# ProPrj___2025-12-10.net
KiCad netlist of a schematic drawn in EasyEDA Pro
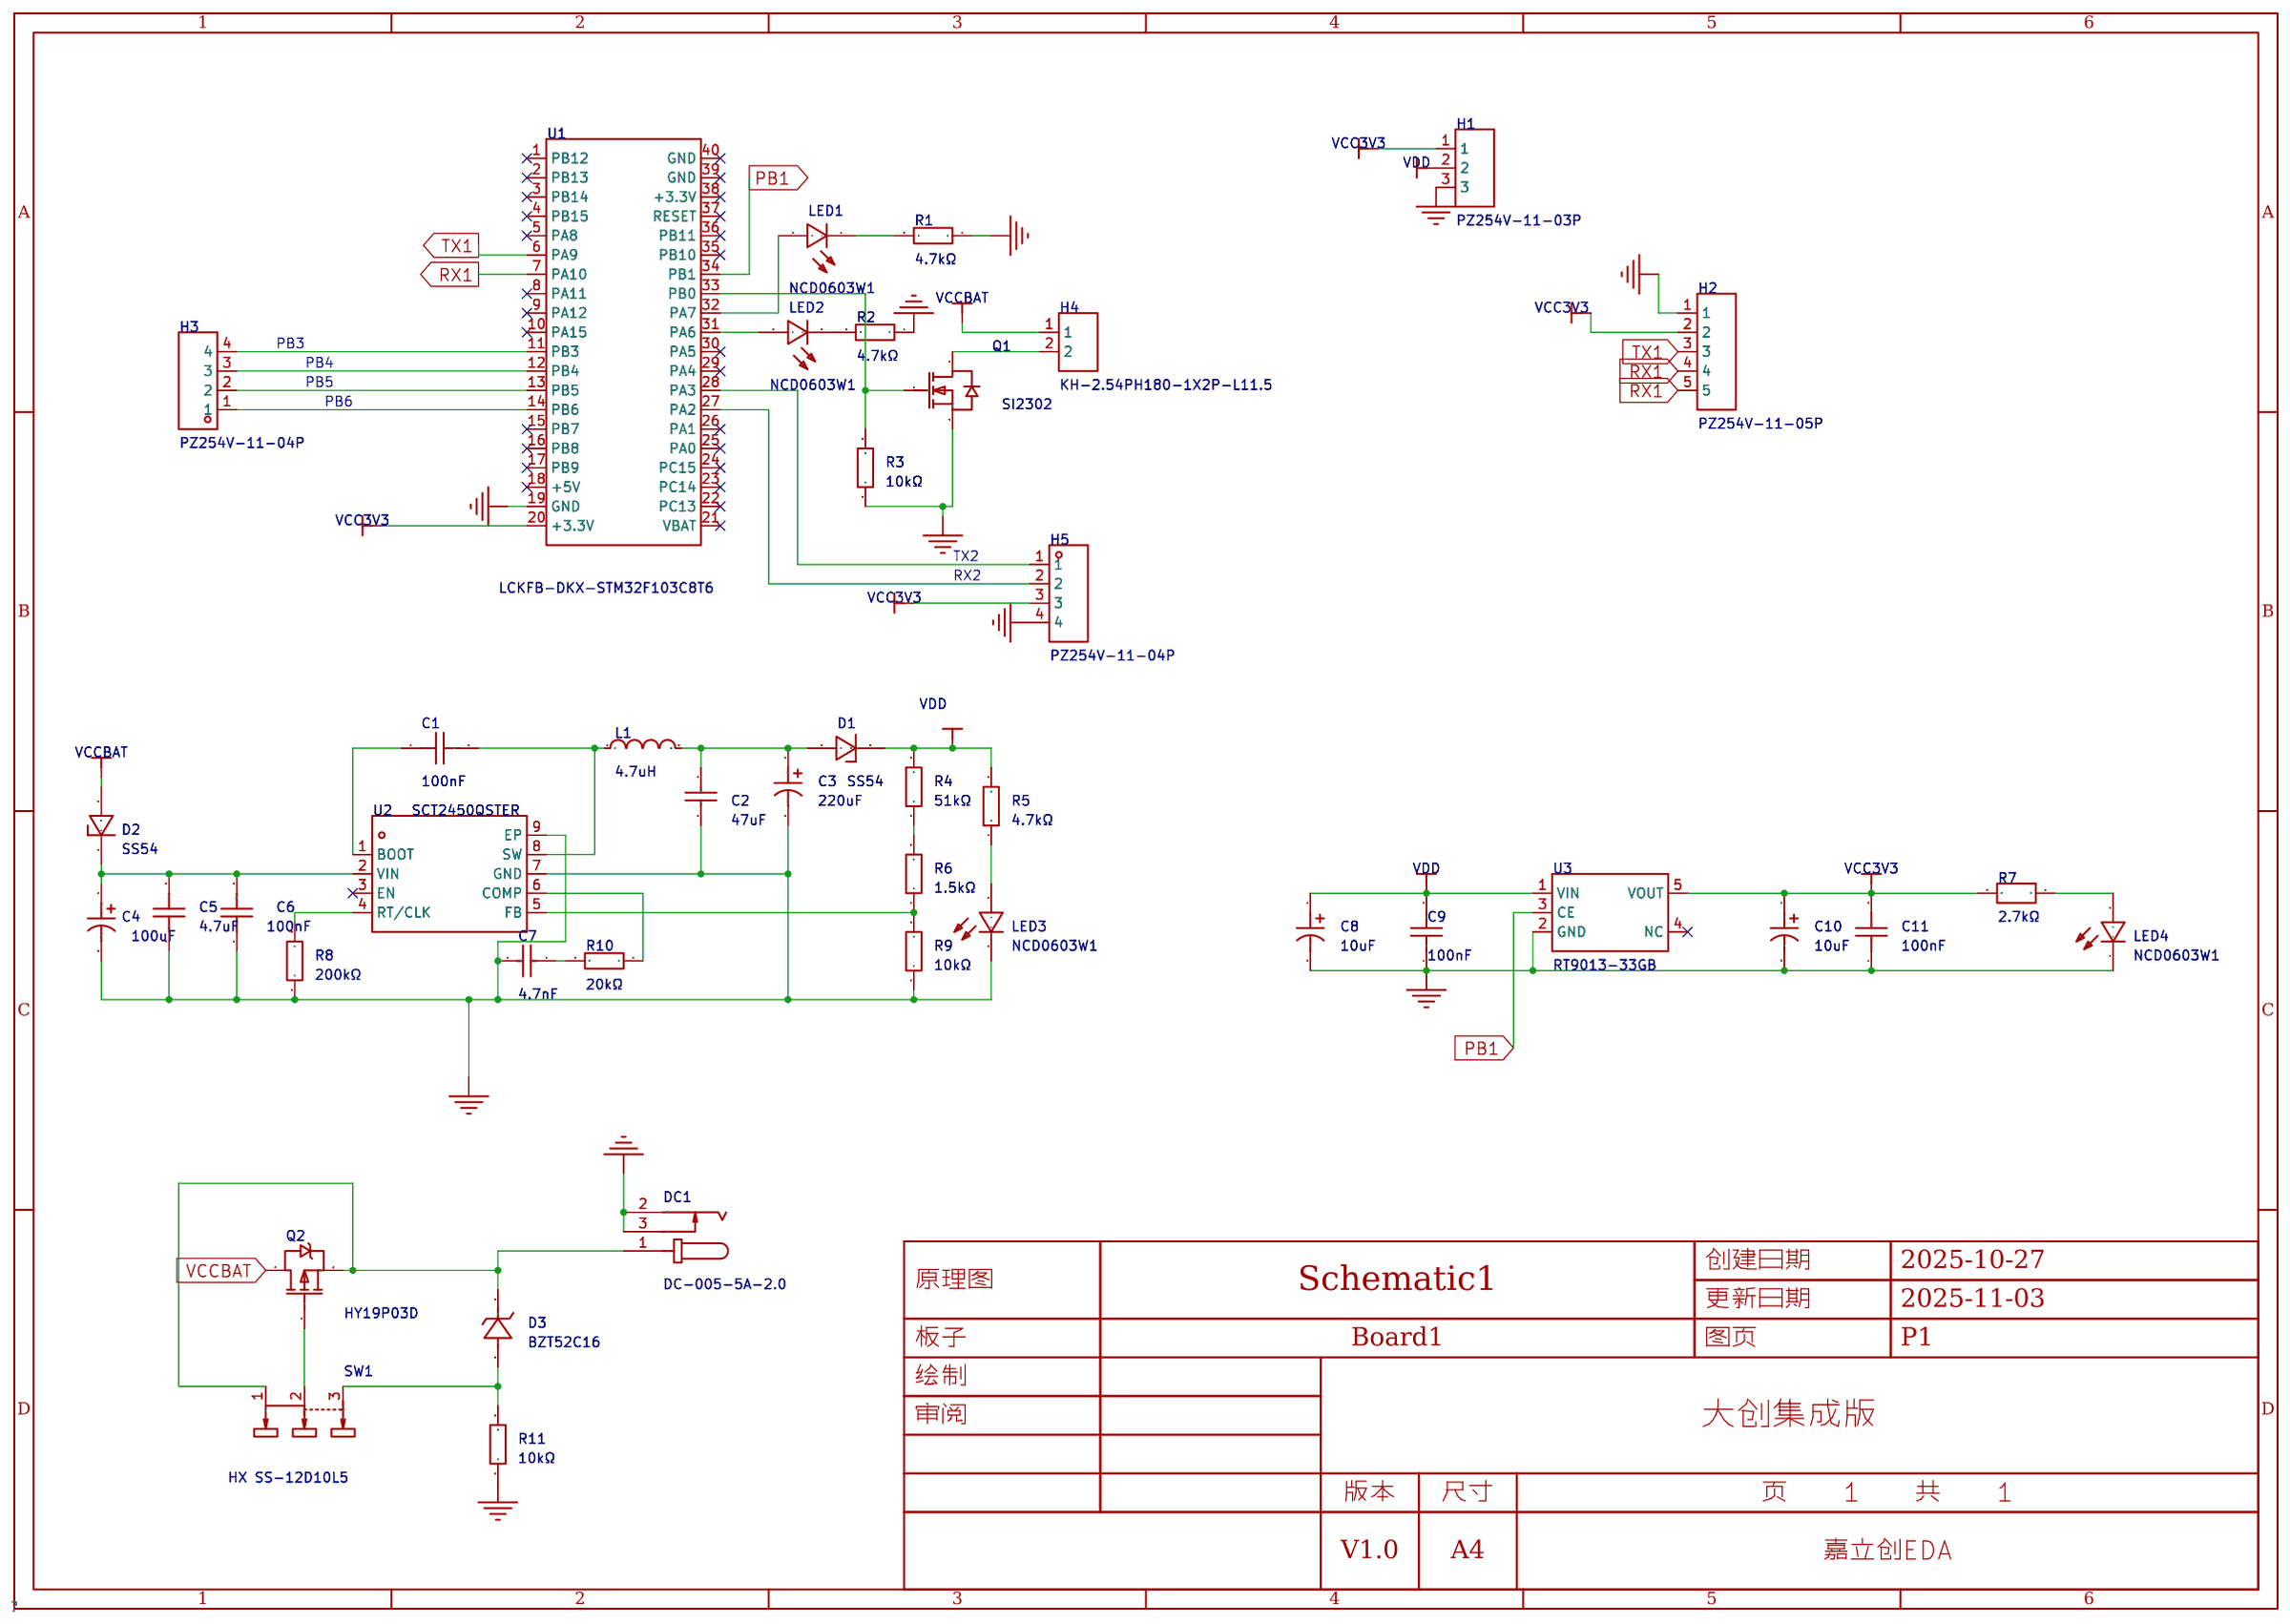
[diagram p0: schematic sheet]

(export (version "E")
  (design (tool "Eeschema 10.0.6"))
  (components
    (comp (ref "C1")
      (value "100nF")
      (footprint "easyedapro:C0603")
      (fields
        (field (name "Manufacturer Part") "CL10B104KB8NNNC")
        (field (name "Manufacturer") "SAMSUNG(三星)")
      )
      (libsource (lib "easyedapro") (part "CL10B104KB8NNNC"))
    )
    (comp (ref "C2")
      (value "47uF")
      (footprint "easyedapro:C0603")
      (fields
        (field (name "Manufacturer Part") "GRM188R60J476ME15D")
        (field (name "Manufacturer") "muRata(村田)")
      )
      (libsource (lib "easyedapro") (part "GRM188R60J476ME15D"))
    )
    (comp (ref "C3")
      (value "220uF")
      (footprint "easyedapro:CAP-SMD_BD6.3-L6.6-W6.6-LS7.3-FD-H7.7")
      (fields (field (name "Manufacturer Part") "JVJ25V220M6x8") (field (name "Manufacturer") "JIERR(捷而瑞)"))
      (libsource (lib "easyedapro") (part "JVJ25V220M6X8"))
    )
    (comp (ref "C4")
      (value "100uF")
      (footprint "easyedapro:CAP-SMD_BD6.3-L6.6-W6.6-FD-1")
      (fields (field (name "Manufacturer Part") "JVJ25V100M6x5") (field (name "Manufacturer") "JIERR(捷而瑞)"))
      (libsource (lib "easyedapro") (part "JVJ25V100M6X5"))
    )
    (comp (ref "C5")
      (value "4.7uF")
      (footprint "easyedapro:C0603")
      (fields
        (field (name "Manufacturer Part") "CL10A475KO8NNNC")
        (field (name "Manufacturer") "SAMSUNG(三星)")
      )
      (libsource (lib "easyedapro") (part "CL10A475KO8NNNC"))
    )
    (comp (ref "C6")
      (value "100nF")
      (footprint "easyedapro:C0603")
      (fields
        (field (name "Manufacturer Part") "CL10B104KB8NNNC")
        (field (name "Manufacturer") "SAMSUNG(三星)")
      )
      (libsource (lib "easyedapro") (part "CL10B104KB8NNNC"))
    )
    (comp (ref "C7")
      (value "4.7nF")
      (footprint "easyedapro:C0603")
      (fields (field (name "Manufacturer Part") "0603B472K500NT") (field (name "Manufacturer") "FH(风华)"))
      (libsource (lib "easyedapro") (part "0603B472K500NT"))
    )
    (comp (ref "C8")
      (value "10uF")
      (footprint "easyedapro:CAP-SMD_BD4.0-L4.3-W4.3-LS5.1-FD")
      (fields (field (name "Manufacturer Part") "JVJ25V10M4x6") (field (name "Manufacturer") "JIERR(捷而瑞)"))
      (libsource (lib "easyedapro") (part "JVJ25V10M4X6"))
    )
    (comp (ref "C9")
      (value "100nF")
      (footprint "easyedapro:C0603")
      (fields
        (field (name "Manufacturer Part") "CL10B104KB8NNNC")
        (field (name "Manufacturer") "SAMSUNG(三星)")
      )
      (libsource (lib "easyedapro") (part "CL10B104KB8NNNC"))
    )
    (comp (ref "C10")
      (value "10uF")
      (footprint "easyedapro:CAP-SMD_BD4.0-L4.3-W4.3-LS5.1-FD")
      (fields (field (name "Manufacturer Part") "JVJ25V10M4x6") (field (name "Manufacturer") "JIERR(捷而瑞)"))
      (libsource (lib "easyedapro") (part "JVJ25V10M4X6"))
    )
    (comp (ref "C11")
      (value "100nF")
      (footprint "easyedapro:C0603")
      (fields
        (field (name "Manufacturer Part") "CL10B104KB8NNNC")
        (field (name "Manufacturer") "SAMSUNG(三星)")
      )
      (libsource (lib "easyedapro") (part "CL10B104KB8NNNC"))
    )
    (comp (ref "D1")
      (value "SS54")
      (footprint "easyedapro:SMA_L4.3-W2.6-LS5.0-FD")
      (fields (field (name "Manufacturer") "R+O(宏嘉诚)"))
      (libsource (lib "easyedapro") (part "SS54_C7420369"))
    )
    (comp (ref "D2")
      (value "SS54")
      (footprint "easyedapro:SMA_L4.3-W2.6-LS5.0-FD")
      (fields (field (name "Manufacturer") "R+O(宏嘉诚)"))
      (libsource (lib "easyedapro") (part "SS54_C7420369"))
    )
    (comp (ref "D3")
      (value "BZT52C16")
      (footprint "easyedapro:SOD-123_L2.7-W1.6-LS3.7-RD")
      (fields (field (name "Manufacturer") "R+O(宏嘉诚)"))
      (libsource (lib "easyedapro") (part "BZT52C16_C19077413"))
    )
    (comp (ref "DC1")
      (value "DC-005-5A-2.0")
      (footprint "easyedapro:DC-IN-TH_DC-005-5A-2.0")
      (fields (field (name "Manufacturer") "XKB Connection(中国星坤)"))
      (libsource (lib "easyedapro") (part "DC-005-5A-2.0"))
    )
    (comp (ref "H1")
      (value "PZ254V-11-03P")
      (footprint "easyedapro:HDR-TH_3P-P2.54-V-M")
      (fields (field (name "Manufacturer") "XFCN(兴飞)"))
      (libsource (lib "easyedapro") (part "PZ254V-11-03P_C2937625"))
    )
    (comp (ref "H2")
      (value "PZ254V-11-05P")
      (footprint "easyedapro:HDR-TH_5P-P2.54-V-M")
      (fields (field (name "Manufacturer") "XFCN(兴飞)"))
      (libsource (lib "easyedapro") (part "PZ254V-11-05P"))
    )
    (comp (ref "H3")
      (value "PZ254V-11-04P")
      (footprint "easyedapro:HDR-TH_4P-P2.54-V-M")
      (fields (field (name "Manufacturer") "XFCN(兴飞)"))
      (libsource (lib "easyedapro") (part "PZ254V-11-04P_C2691448"))
    )
    (comp (ref "H4")
      (value "KH-2.54PH180-1X2P-L11.5")
      (footprint "easyedapro:HDR-TH_2P-P2.54-V-M")
      (fields (field (name "Manufacturer") "kinghelm(金航标)"))
      (libsource (lib "easyedapro") (part "KH-2.54PH180-1X2P-L11.5"))
    )
    (comp (ref "H5")
      (value "PZ254V-11-04P")
      (footprint "easyedapro:HDR-TH_4P-P2.54-V-M")
      (fields (field (name "Manufacturer") "XFCN(兴飞)"))
      (libsource (lib "easyedapro") (part "PZ254V-11-04P_C2691448"))
    )
    (comp (ref "L1")
      (value "4.7uH")
      (footprint "easyedapro:IND-SMD_L4.0-W4.0_FNR40XXS")
      (fields (field (name "Manufacturer Part") "FNR4030S4R7MT") (field (name "Manufacturer") "cjiang(长江微电)"))
      (libsource (lib "easyedapro") (part "FNR4030S4R7MT"))
    )
    (comp (ref "LED1")
      (value "NCD0603W1")
      (footprint "easyedapro:LED0603-RD")
      (fields (field (name "Manufacturer") "国星光电"))
      (libsource (lib "easyedapro") (part "NCD0603W1"))
    )
    (comp (ref "LED2")
      (value "NCD0603W1")
      (footprint "easyedapro:LED0603-RD")
      (fields (field (name "Manufacturer") "国星光电"))
      (libsource (lib "easyedapro") (part "NCD0603W1"))
    )
    (comp (ref "LED3")
      (value "NCD0603W1")
      (footprint "easyedapro:LED0603-RD")
      (fields (field (name "Manufacturer") "国星光电"))
      (libsource (lib "easyedapro") (part "NCD0603W1"))
    )
    (comp (ref "LED4")
      (value "NCD0603W1")
      (footprint "easyedapro:LED0603-RD")
      (fields (field (name "Manufacturer") "国星光电"))
      (libsource (lib "easyedapro") (part "NCD0603W1"))
    )
    (comp (ref "Q1")
      (value "SI2302")
      (footprint "easyedapro:SOT-23-3_L2.9-W1.3-P1.90-LS2.4-BR")
      (fields (field (name "Manufacturer") "YONGYUTAI(永裕泰)"))
      (libsource (lib "easyedapro") (part "SI2302_C2891732"))
    )
    (comp (ref "Q2")
      (value "HY19P03D")
      (footprint "easyedapro:TO-252-2_L6.6-W6.1-P4.57-LS9.9-TL-CW")
      (fields (field (name "Manufacturer") "HUAYI(华羿微)"))
      (libsource (lib "easyedapro") (part "HY19P03D"))
    )
    (comp (ref "R1")
      (value "4.7kΩ")
      (footprint "easyedapro:R0603")
      (fields
        (field (name "Manufacturer Part") "0603WAF4701T5E")
        (field (name "Manufacturer") "UNI-ROYAL(厚声)")
      )
      (libsource (lib "easyedapro") (part "0603WAF4701T5E"))
    )
    (comp (ref "R2")
      (value "4.7kΩ")
      (footprint "easyedapro:R0603")
      (fields
        (field (name "Manufacturer Part") "0603WAF4701T5E")
        (field (name "Manufacturer") "UNI-ROYAL(厚声)")
      )
      (libsource (lib "easyedapro") (part "0603WAF4701T5E"))
    )
    (comp (ref "R3")
      (value "10kΩ")
      (footprint "easyedapro:R0603")
      (fields
        (field (name "Manufacturer Part") "0603WAF1002T5E")
        (field (name "Manufacturer") "UNI-ROYAL(厚声)")
      )
      (libsource (lib "easyedapro") (part "0603WAF1002T5E"))
    )
    (comp (ref "R4")
      (value "51kΩ")
      (footprint "easyedapro:R0603")
      (fields
        (field (name "Manufacturer Part") "0603WAF5102T5E")
        (field (name "Manufacturer") "UNI-ROYAL(厚声)")
      )
      (libsource (lib "easyedapro") (part "0603WAF5102T5E"))
    )
    (comp (ref "R5")
      (value "4.7kΩ")
      (footprint "easyedapro:R0603")
      (fields
        (field (name "Manufacturer Part") "0603WAF4701T5E")
        (field (name "Manufacturer") "UNI-ROYAL(厚声)")
      )
      (libsource (lib "easyedapro") (part "0603WAF4701T5E"))
    )
    (comp (ref "R6")
      (value "1.5kΩ")
      (footprint "easyedapro:R0603")
      (fields
        (field (name "Manufacturer Part") "0603WAF1501T5E")
        (field (name "Manufacturer") "UNI-ROYAL(厚声)")
      )
      (libsource (lib "easyedapro") (part "0603WAF1501T5E"))
    )
    (comp (ref "R7")
      (value "2.7kΩ")
      (footprint "easyedapro:R0603")
      (fields (field (name "Manufacturer Part") "FRC0603F2701TS") (field (name "Manufacturer") "FOJAN(富捷)"))
      (libsource (lib "easyedapro") (part "FRC0603F2701TS"))
    )
    (comp (ref "R8")
      (value "200kΩ")
      (footprint "easyedapro:R0603")
      (fields
        (field (name "Manufacturer Part") "0603WAF2003T5E")
        (field (name "Manufacturer") "UNI-ROYAL(厚声)")
      )
      (libsource (lib "easyedapro") (part "0603WAF2003T5E"))
    )
    (comp (ref "R9")
      (value "10kΩ")
      (footprint "easyedapro:R0603")
      (fields
        (field (name "Manufacturer Part") "0603WAF1002T5E")
        (field (name "Manufacturer") "UNI-ROYAL(厚声)")
      )
      (libsource (lib "easyedapro") (part "0603WAF1002T5E"))
    )
    (comp (ref "R10")
      (value "20kΩ")
      (footprint "easyedapro:R0603")
      (fields
        (field (name "Manufacturer Part") "0603WAF2002T5E")
        (field (name "Manufacturer") "UNI-ROYAL(厚声)")
      )
      (libsource (lib "easyedapro") (part "0603WAF2002T5E"))
    )
    (comp (ref "R11")
      (value "10kΩ")
      (footprint "easyedapro:R0603")
      (fields
        (field (name "Manufacturer Part") "0603WAF1002T5E")
        (field (name "Manufacturer") "UNI-ROYAL(厚声)")
      )
      (libsource (lib "easyedapro") (part "0603WAF1002T5E"))
    )
    (comp (ref "SW1")
      (value "HX SS-12D10L5")
      (footprint "easyedapro:SW-TH_HX-SS-12D10L5")
      (fields (field (name "Manufacturer") "hanxia(韩下)"))
      (libsource (lib "easyedapro") (part "HX SS-12D10L5"))
    )
    (comp (ref "U1")
      (value "LCKFB-DKX-STM32F103C8T6")
      (footprint "easyedapro:CONN-TH_L53.3-W22.9_STM32F103C8T6-CARD")
      (fields (field (name "Manufacturer") "立创开发板"))
      (libsource (lib "easyedapro") (part "LCKFB-DKX-STM32F103C8T6"))
    )
    (comp (ref "U2")
      (value "SCT2450QSTER")
      (footprint "easyedapro:ESOP-8_L4.9-W3.9-P1.27-LS6.0-BL-EP")
      (fields (field (name "Manufacturer") "SCT(芯洲科技)"))
      (libsource (lib "easyedapro") (part "SCT2450QSTER"))
    )
    (comp (ref "U3")
      (value "RT9013-33GB")
      (footprint "easyedapro:SOT-23-5_L2.9-W1.6-P0.95-LS2.8-BR")
      (fields (field (name "Manufacturer") "TECH PUBLIC(台舟)"))
      (libsource (lib "easyedapro") (part "RT9013-33GB_C19268157"))
    )
  )
  (nets
    (net (code "1") (name "/PB3") (class "Default")
      (node (ref "H3") (pin "4") (pinfunction "4_4") (pintype "unspecified"))
      (node (ref "U1") (pin "11") (pinfunction "PB3_11") (pintype "unspecified"))
    )
    (net (code "2") (name "/PB4") (class "Default")
      (node (ref "H3") (pin "3") (pinfunction "3_3") (pintype "unspecified"))
      (node (ref "U1") (pin "12") (pinfunction "PB4_12") (pintype "unspecified"))
    )
    (net (code "3") (name "/PB5") (class "Default")
      (node (ref "H3") (pin "2") (pinfunction "2_2") (pintype "unspecified"))
      (node (ref "U1") (pin "13") (pinfunction "PB5_13") (pintype "unspecified"))
    )
    (net (code "4") (name "/PB6") (class "Default")
      (node (ref "H3") (pin "1") (pinfunction "1_1") (pintype "unspecified"))
      (node (ref "U1") (pin "14") (pinfunction "PB6_14") (pintype "unspecified"))
    )
    (net (code "5") (name "/RX2") (class "Default")
      (node (ref "H5") (pin "2") (pinfunction "2_2") (pintype "unspecified"))
      (node (ref "U1") (pin "27") (pinfunction "PA2_27") (pintype "unspecified"))
    )
    (net (code "6") (name "/TX2") (class "Default")
      (node (ref "H5") (pin "1") (pinfunction "1_1") (pintype "unspecified"))
      (node (ref "U1") (pin "28") (pinfunction "PA3_28") (pintype "unspecified"))
    )
    (net (code "7") (name "GND") (class "Default")
      (node (ref "C10") (pin "2") (pinfunction "2_2") (pintype "input"))
      (node (ref "C11") (pin "1") (pinfunction "1_1") (pintype "unspecified"))
      (node (ref "C2") (pin "1") (pinfunction "1_1") (pintype "input"))
      (node (ref "C3") (pin "2") (pinfunction "2_2") (pintype "input"))
      (node (ref "C4") (pin "2") (pinfunction "2_2") (pintype "input"))
      (node (ref "C5") (pin "1") (pinfunction "1_1") (pintype "unspecified"))
      (node (ref "C6") (pin "1") (pinfunction "1_1") (pintype "unspecified"))
      (node (ref "C7") (pin "1") (pinfunction "1_1") (pintype "input"))
      (node (ref "C8") (pin "2") (pinfunction "2_2") (pintype "input"))
      (node (ref "C9") (pin "1") (pinfunction "1_1") (pintype "unspecified"))
      (node (ref "DC1") (pin "2") (pinfunction "2_2") (pintype "unspecified"))
      (node (ref "DC1") (pin "3") (pinfunction "3_3") (pintype "unspecified"))
      (node (ref "H1") (pin "3") (pinfunction "3_3") (pintype "unspecified"))
      (node (ref "H2") (pin "1") (pinfunction "1_1") (pintype "unspecified"))
      (node (ref "H5") (pin "4") (pinfunction "4_4") (pintype "unspecified"))
      (node (ref "LED3") (pin "1") (pinfunction "-_1") (pintype "input"))
      (node (ref "LED4") (pin "1") (pinfunction "-_1") (pintype "input"))
      (node (ref "Q1") (pin "2") (pinfunction "S_2") (pintype "unspecified"))
      (node (ref "R1") (pin "1") (pinfunction "1_1") (pintype "input"))
      (node (ref "R11") (pin "1") (pinfunction "1_1") (pintype "input"))
      (node (ref "R2") (pin "1") (pinfunction "1_1") (pintype "input"))
      (node (ref "R3") (pin "1") (pinfunction "1_1") (pintype "input"))
      (node (ref "R8") (pin "1") (pinfunction "1_1") (pintype "input"))
      (node (ref "R9") (pin "1") (pinfunction "1_1") (pintype "input"))
      (node (ref "U1") (pin "19") (pinfunction "GND_19") (pintype "unspecified"))
      (node (ref "U2") (pin "7") (pinfunction "GND_7") (pintype "unspecified"))
      (node (ref "U2") (pin "9") (pinfunction "EP_9") (pintype "unspecified"))
      (node (ref "U3") (pin "2") (pinfunction "GND_2") (pintype "unspecified"))
    )
    (net (code "8") (name "Net-(C7-Pad2)") (class "Default")
      (node (ref "C7") (pin "2") (pinfunction "2_2") (pintype "input"))
      (node (ref "R10") (pin "2") (pinfunction "2_2") (pintype "input"))
    )
    (net (code "9") (name "Net-(D1-A)") (class "Default")
      (node (ref "C2") (pin "2") (pinfunction "2_2") (pintype "input"))
      (node (ref "C3") (pin "1") (pinfunction "1_1") (pintype "input"))
      (node (ref "D1") (pin "1") (pinfunction "A_1") (pintype "unspecified"))
      (node (ref "L1") (pin "2") (pinfunction "2_2") (pintype "unspecified"))
    )
    (net (code "10") (name "Net-(D2-K)") (class "Default")
      (node (ref "C4") (pin "1") (pinfunction "1_1") (pintype "input"))
      (node (ref "C5") (pin "2") (pinfunction "2_2") (pintype "unspecified"))
      (node (ref "C6") (pin "2") (pinfunction "2_2") (pintype "unspecified"))
      (node (ref "D2") (pin "2") (pinfunction "K_2") (pintype "unspecified"))
      (node (ref "U2") (pin "2") (pinfunction "VIN_2") (pintype "unspecified"))
    )
    (net (code "11") (name "Net-(D3-A)") (class "Default")
      (node (ref "D3") (pin "2") (pinfunction "A_2") (pintype "unspecified"))
      (node (ref "R11") (pin "2") (pinfunction "2_2") (pintype "input"))
      (node (ref "SW1") (pin "3") (pinfunction "3_3") (pintype "unspecified"))
    )
    (net (code "12") (name "Net-(D3-K)") (class "Default")
      (node (ref "D3") (pin "1") (pinfunction "K_1") (pintype "unspecified"))
      (node (ref "DC1") (pin "1") (pinfunction "1_1") (pintype "unspecified"))
      (node (ref "Q2") (pin "3") (pinfunction "S_3") (pintype "unspecified"))
      (node (ref "SW1") (pin "1") (pinfunction "1_1") (pintype "unspecified"))
    )
    (net (code "13") (name "Net-(LED1-+)") (class "Default")
      (node (ref "LED1") (pin "2") (pinfunction "+_2") (pintype "input"))
      (node (ref "U1") (pin "32") (pinfunction "PA7_32") (pintype "unspecified"))
    )
    (net (code "14") (name "Net-(LED1--)") (class "Default")
      (node (ref "LED1") (pin "1") (pinfunction "-_1") (pintype "input"))
      (node (ref "R1") (pin "2") (pinfunction "2_2") (pintype "input"))
    )
    (net (code "15") (name "Net-(LED2-+)") (class "Default")
      (node (ref "LED2") (pin "2") (pinfunction "+_2") (pintype "input"))
      (node (ref "U1") (pin "31") (pinfunction "PA6_31") (pintype "unspecified"))
    )
    (net (code "16") (name "Net-(LED2--)") (class "Default")
      (node (ref "LED2") (pin "1") (pinfunction "-_1") (pintype "input"))
      (node (ref "R2") (pin "2") (pinfunction "2_2") (pintype "input"))
    )
    (net (code "17") (name "Net-(LED3-+)") (class "Default")
      (node (ref "LED3") (pin "2") (pinfunction "+_2") (pintype "input"))
      (node (ref "R5") (pin "1") (pinfunction "1_1") (pintype "input"))
    )
    (net (code "18") (name "Net-(LED4-+)") (class "Default")
      (node (ref "LED4") (pin "2") (pinfunction "+_2") (pintype "input"))
      (node (ref "R7") (pin "1") (pinfunction "1_1") (pintype "unspecified"))
    )
    (net (code "19") (name "Net-(Q1-D)") (class "Default")
      (node (ref "H4") (pin "2") (pinfunction "2_2") (pintype "unspecified"))
      (node (ref "Q1") (pin "3") (pinfunction "D_3") (pintype "unspecified"))
    )
    (net (code "20") (name "Net-(Q1-G)") (class "Default")
      (node (ref "Q1") (pin "1") (pinfunction "G_1") (pintype "unspecified"))
      (node (ref "R3") (pin "2") (pinfunction "2_2") (pintype "input"))
      (node (ref "U1") (pin "33") (pinfunction "PB0_33") (pintype "unspecified"))
    )
    (net (code "21") (name "Net-(Q2-G)") (class "Default")
      (node (ref "Q2") (pin "1") (pinfunction "G_1") (pintype "unspecified"))
      (node (ref "SW1") (pin "2") (pinfunction "2_2") (pintype "unspecified"))
    )
    (net (code "22") (name "Net-(R4-Pad1)") (class "Default")
      (node (ref "R4") (pin "1") (pinfunction "1_1") (pintype "input"))
      (node (ref "R6") (pin "2") (pinfunction "2_2") (pintype "input"))
    )
    (net (code "23") (name "Net-(U2-BOOT)") (class "Default")
      (node (ref "C1") (pin "1") (pinfunction "1_1") (pintype "unspecified"))
      (node (ref "U2") (pin "1") (pinfunction "BOOT_1") (pintype "unspecified"))
    )
    (net (code "24") (name "Net-(U2-COMP)") (class "Default")
      (node (ref "R10") (pin "1") (pinfunction "1_1") (pintype "input"))
      (node (ref "U2") (pin "6") (pinfunction "COMP_6") (pintype "unspecified"))
    )
    (net (code "25") (name "Net-(U2-FB)") (class "Default")
      (node (ref "R6") (pin "1") (pinfunction "1_1") (pintype "input"))
      (node (ref "R9") (pin "2") (pinfunction "2_2") (pintype "input"))
      (node (ref "U2") (pin "5") (pinfunction "FB_5") (pintype "unspecified"))
    )
    (net (code "26") (name "Net-(U2-RT{slash}CLK)") (class "Default")
      (node (ref "R8") (pin "2") (pinfunction "2_2") (pintype "input"))
      (node (ref "U2") (pin "4") (pinfunction "RT/CLK_4") (pintype "unspecified"))
    )
    (net (code "27") (name "Net-(U2-SW)") (class "Default")
      (node (ref "C1") (pin "2") (pinfunction "2_2") (pintype "unspecified"))
      (node (ref "L1") (pin "1") (pinfunction "1_1") (pintype "unspecified"))
      (node (ref "U2") (pin "8") (pinfunction "SW_8") (pintype "unspecified"))
    )
    (net (code "28") (name "PB1") (class "Default")
      (node (ref "U1") (pin "34") (pinfunction "PB1_34") (pintype "unspecified"))
      (node (ref "U3") (pin "3") (pinfunction "CE_3") (pintype "unspecified"))
    )
    (net (code "29") (name "RX1") (class "Default")
      (node (ref "H2") (pin "4") (pinfunction "4_4") (pintype "unspecified"))
      (node (ref "H2") (pin "5") (pinfunction "5_5") (pintype "unspecified"))
      (node (ref "U1") (pin "7") (pinfunction "PA10_7") (pintype "unspecified"))
    )
    (net (code "30") (name "TX1") (class "Default")
      (node (ref "H2") (pin "3") (pinfunction "3_3") (pintype "unspecified"))
      (node (ref "U1") (pin "6") (pinfunction "PA9_6") (pintype "unspecified"))
    )
    (net (code "31") (name "VCC3V3") (class "Default")
      (node (ref "C10") (pin "1") (pinfunction "1_1") (pintype "input"))
      (node (ref "C11") (pin "2") (pinfunction "2_2") (pintype "unspecified"))
      (node (ref "H1") (pin "1") (pinfunction "1_1") (pintype "unspecified"))
      (node (ref "H2") (pin "2") (pinfunction "2_2") (pintype "unspecified"))
      (node (ref "H5") (pin "3") (pinfunction "3_3") (pintype "unspecified"))
      (node (ref "R7") (pin "2") (pinfunction "2_2") (pintype "unspecified"))
      (node (ref "U1") (pin "20") (pinfunction "+3.3V_20") (pintype "unspecified"))
      (node (ref "U3") (pin "5") (pinfunction "VOUT_5") (pintype "unspecified"))
    )
    (net (code "32") (name "VCCBAT") (class "Default")
      (node (ref "D2") (pin "1") (pinfunction "A_1") (pintype "unspecified"))
      (node (ref "H4") (pin "1") (pinfunction "1_1") (pintype "unspecified"))
      (node (ref "Q2") (pin "2") (pinfunction "D_2") (pintype "unspecified"))
    )
    (net (code "33") (name "VDD") (class "Default")
      (node (ref "C8") (pin "1") (pinfunction "1_1") (pintype "input"))
      (node (ref "C9") (pin "2") (pinfunction "2_2") (pintype "unspecified"))
      (node (ref "D1") (pin "2") (pinfunction "K_2") (pintype "unspecified"))
      (node (ref "H1") (pin "2") (pinfunction "2_2") (pintype "unspecified"))
      (node (ref "R4") (pin "2") (pinfunction "2_2") (pintype "input"))
      (node (ref "R5") (pin "2") (pinfunction "2_2") (pintype "input"))
      (node (ref "U3") (pin "1") (pinfunction "VIN_1") (pintype "unspecified"))
    )
    (net (code "34") (name "unconnected-(U1-+3.3V-Pad38)") (class "Default")
      (node (ref "U1") (pin "38") (pinfunction "+3.3V_38") (pintype "unspecified+no_connect"))
    )
    (net (code "35") (name "unconnected-(U1-+5V-Pad18)") (class "Default")
      (node (ref "U1") (pin "18") (pinfunction "+5V_18") (pintype "unspecified+no_connect"))
    )
    (net (code "36") (name "unconnected-(U1-GND-Pad39)") (class "Default")
      (node (ref "U1") (pin "39") (pinfunction "GND_39") (pintype "unspecified+no_connect"))
    )
    (net (code "37") (name "unconnected-(U1-GND-Pad40)") (class "Default")
      (node (ref "U1") (pin "40") (pinfunction "GND_40") (pintype "unspecified+no_connect"))
    )
    (net (code "38") (name "unconnected-(U1-PA0-Pad25)") (class "Default")
      (node (ref "U1") (pin "25") (pinfunction "PA0_25") (pintype "unspecified+no_connect"))
    )
    (net (code "39") (name "unconnected-(U1-PA1-Pad26)") (class "Default")
      (node (ref "U1") (pin "26") (pinfunction "PA1_26") (pintype "unspecified+no_connect"))
    )
    (net (code "40") (name "unconnected-(U1-PA4-Pad29)") (class "Default")
      (node (ref "U1") (pin "29") (pinfunction "PA4_29") (pintype "unspecified+no_connect"))
    )
    (net (code "41") (name "unconnected-(U1-PA5-Pad30)") (class "Default")
      (node (ref "U1") (pin "30") (pinfunction "PA5_30") (pintype "unspecified+no_connect"))
    )
    (net (code "42") (name "unconnected-(U1-PA8-Pad5)") (class "Default")
      (node (ref "U1") (pin "5") (pinfunction "PA8_5") (pintype "unspecified+no_connect"))
    )
    (net (code "43") (name "unconnected-(U1-PA11-Pad8)") (class "Default")
      (node (ref "U1") (pin "8") (pinfunction "PA11_8") (pintype "unspecified+no_connect"))
    )
    (net (code "44") (name "unconnected-(U1-PA12-Pad9)") (class "Default")
      (node (ref "U1") (pin "9") (pinfunction "PA12_9") (pintype "unspecified+no_connect"))
    )
    (net (code "45") (name "unconnected-(U1-PA15-Pad10)") (class "Default")
      (node (ref "U1") (pin "10") (pinfunction "PA15_10") (pintype "unspecified+no_connect"))
    )
    (net (code "46") (name "unconnected-(U1-PB7-Pad15)") (class "Default")
      (node (ref "U1") (pin "15") (pinfunction "PB7_15") (pintype "unspecified+no_connect"))
    )
    (net (code "47") (name "unconnected-(U1-PB8-Pad16)") (class "Default")
      (node (ref "U1") (pin "16") (pinfunction "PB8_16") (pintype "unspecified+no_connect"))
    )
    (net (code "48") (name "unconnected-(U1-PB9-Pad17)") (class "Default")
      (node (ref "U1") (pin "17") (pinfunction "PB9_17") (pintype "unspecified+no_connect"))
    )
    (net (code "49") (name "unconnected-(U1-PB10-Pad35)") (class "Default")
      (node (ref "U1") (pin "35") (pinfunction "PB10_35") (pintype "unspecified+no_connect"))
    )
    (net (code "50") (name "unconnected-(U1-PB11-Pad36)") (class "Default")
      (node (ref "U1") (pin "36") (pinfunction "PB11_36") (pintype "unspecified+no_connect"))
    )
    (net (code "51") (name "unconnected-(U1-PB12-Pad1)") (class "Default")
      (node (ref "U1") (pin "1") (pinfunction "PB12_1") (pintype "unspecified+no_connect"))
    )
    (net (code "52") (name "unconnected-(U1-PB13-Pad2)") (class "Default")
      (node (ref "U1") (pin "2") (pinfunction "PB13_2") (pintype "unspecified+no_connect"))
    )
    (net (code "53") (name "unconnected-(U1-PB14-Pad3)") (class "Default")
      (node (ref "U1") (pin "3") (pinfunction "PB14_3") (pintype "unspecified+no_connect"))
    )
    (net (code "54") (name "unconnected-(U1-PB15-Pad4)") (class "Default")
      (node (ref "U1") (pin "4") (pinfunction "PB15_4") (pintype "unspecified+no_connect"))
    )
    (net (code "55") (name "unconnected-(U1-PC13-Pad22)") (class "Default")
      (node (ref "U1") (pin "22") (pinfunction "PC13_22") (pintype "unspecified+no_connect"))
    )
    (net (code "56") (name "unconnected-(U1-PC14-Pad23)") (class "Default")
      (node (ref "U1") (pin "23") (pinfunction "PC14_23") (pintype "unspecified+no_connect"))
    )
    (net (code "57") (name "unconnected-(U1-PC15-Pad24)") (class "Default")
      (node (ref "U1") (pin "24") (pinfunction "PC15_24") (pintype "unspecified+no_connect"))
    )
    (net (code "58") (name "unconnected-(U1-RESET-Pad37)") (class "Default")
      (node (ref "U1") (pin "37") (pinfunction "RESET_37") (pintype "unspecified+no_connect"))
    )
    (net (code "59") (name "unconnected-(U1-VBAT-Pad21)") (class "Default")
      (node (ref "U1") (pin "21") (pinfunction "VBAT_21") (pintype "unspecified+no_connect"))
    )
    (net (code "60") (name "unconnected-(U2-EN-Pad3)") (class "Default")
      (node (ref "U2") (pin "3") (pinfunction "EN_3") (pintype "unspecified+no_connect"))
    )
    (net (code "61") (name "unconnected-(U3-NC-Pad4)") (class "Default")
      (node (ref "U3") (pin "4") (pinfunction "NC_4") (pintype "unspecified+no_connect"))
    )
  )
)
